# pl2303.net
KiCad netlist of a schematic drawn in EAGLE
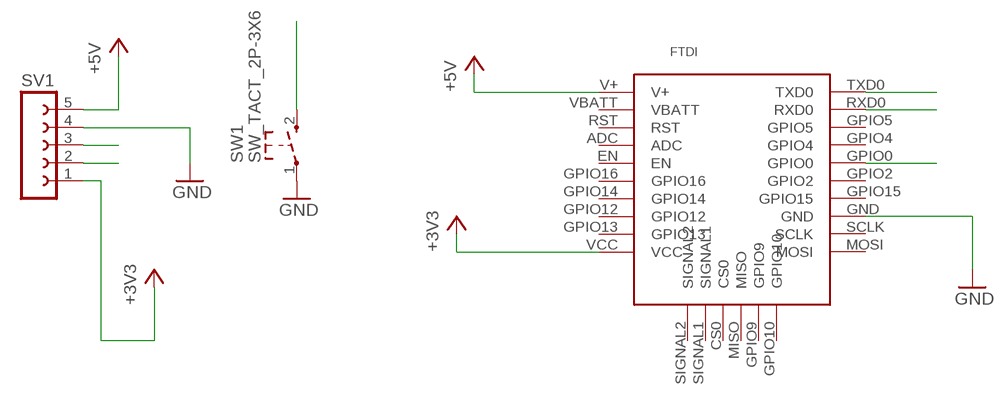
[diagram p0: schematic, sheet 1]

(export (version "E")
  (design (tool "Eeschema 10.0.6"))
  (components
    (comp (ref "FTDI")
      (value "ESP-BOARD")
      (footprint "eagle-import:ESP-BOARD")
      (libsource (lib "eagle-import") (part "ESP-BOARD"))
    )
    (comp (ref "SV1")
      (value "FE05-1")
      (footprint "eagle-import:FE05-1")
      (libsource (lib "eagle-import") (part "FE05-1"))
    )
    (comp (ref "SW1")
      (value "SW_TACT_2P-3X6")
      (footprint "eagle-import:SW_TACT_3X6")
      (libsource (lib "eagle-import") (part "SW_TACT_2P-3X6"))
    )
  )
  (nets
    (net (code "1") (name "+3V3") (class "Default")
      (node (ref "FTDI") (pin "VCC") (pinfunction "VCC_VCC") (pintype "power_in"))
      (node (ref "SV1") (pin "1") (pinfunction "1_1") (pintype "passive"))
    )
    (net (code "2") (name "+5V") (class "Default")
      (node (ref "FTDI") (pin "V+") (pinfunction "V+_V+") (pintype "power_in"))
      (node (ref "SV1") (pin "5") (pinfunction "5_5") (pintype "passive"))
    )
    (net (code "3") (name "/GPIO0") (class "Default")
      (node (ref "FTDI") (pin "GPIO0") (pinfunction "GPIO0_GPIO0") (pintype "bidirectional"))
      (node (ref "SW1") (pin "2") (pinfunction "3_2") (pintype "passive"))
    )
    (net (code "4") (name "/RXD0") (class "Default")
      (node (ref "FTDI") (pin "RXD0") (pinfunction "RXD0_RXD0") (pintype "bidirectional"))
      (node (ref "SV1") (pin "2") (pinfunction "2_2") (pintype "passive"))
    )
    (net (code "5") (name "/TXD0") (class "Default")
      (node (ref "FTDI") (pin "TXD0") (pinfunction "TXD0_TXD0") (pintype "bidirectional"))
      (node (ref "SV1") (pin "3") (pinfunction "3_3") (pintype "passive"))
    )
    (net (code "6") (name "/VBATT") (class "Default")
      (node (ref "FTDI") (pin "VBATT") (pinfunction "VBATT_VBATT") (pintype "power_in"))
    )
    (net (code "7") (name "GND") (class "Default")
      (node (ref "FTDI") (pin "GND") (pinfunction "GND_GND") (pintype "power_in"))
      (node (ref "SV1") (pin "4") (pinfunction "4_4") (pintype "passive"))
      (node (ref "SW1") (pin "1") (pinfunction "1_1") (pintype "passive"))
    )
    (net (code "8") (name "unconnected-(FTDI-PadADC)") (class "Default")
      (node (ref "FTDI") (pin "ADC") (pinfunction "ADC_ADC") (pintype "bidirectional"))
    )
    (net (code "9") (name "unconnected-(FTDI-PadCS0)") (class "Default")
      (node (ref "FTDI") (pin "CS0") (pinfunction "CS0_CS0") (pintype "bidirectional"))
    )
    (net (code "10") (name "unconnected-(FTDI-PadEN)") (class "Default")
      (node (ref "FTDI") (pin "EN") (pinfunction "EN_EN") (pintype "bidirectional"))
    )
    (net (code "11") (name "unconnected-(FTDI-PadGPIO2)") (class "Default")
      (node (ref "FTDI") (pin "GPIO2") (pinfunction "GPIO2_GPIO2") (pintype "bidirectional"))
    )
    (net (code "12") (name "unconnected-(FTDI-PadGPIO4)") (class "Default")
      (node (ref "FTDI") (pin "GPIO4") (pinfunction "GPIO4_GPIO4") (pintype "bidirectional"))
    )
    (net (code "13") (name "unconnected-(FTDI-PadGPIO5)") (class "Default")
      (node (ref "FTDI") (pin "GPIO5") (pinfunction "GPIO5_GPIO5") (pintype "bidirectional"))
    )
    (net (code "14") (name "unconnected-(FTDI-PadGPIO9)") (class "Default")
      (node (ref "FTDI") (pin "GPIO9") (pinfunction "GPIO9_GPIO9") (pintype "bidirectional"))
    )
    (net (code "15") (name "unconnected-(FTDI-PadGPIO10)") (class "Default")
      (node (ref "FTDI") (pin "GPIO10") (pinfunction "GPIO10_GPIO10") (pintype "bidirectional"))
    )
    (net (code "16") (name "unconnected-(FTDI-PadGPIO12)") (class "Default")
      (node (ref "FTDI") (pin "GPIO12") (pinfunction "GPIO12_GPIO12") (pintype "bidirectional"))
    )
    (net (code "17") (name "unconnected-(FTDI-PadGPIO13)") (class "Default")
      (node (ref "FTDI") (pin "GPIO13") (pinfunction "GPIO13_GPIO13") (pintype "bidirectional"))
    )
    (net (code "18") (name "unconnected-(FTDI-PadGPIO14)") (class "Default")
      (node (ref "FTDI") (pin "GPIO14") (pinfunction "GPIO14_GPIO14") (pintype "bidirectional"))
    )
    (net (code "19") (name "unconnected-(FTDI-PadGPIO15)") (class "Default")
      (node (ref "FTDI") (pin "GPIO15") (pinfunction "GPIO15_GPIO15") (pintype "bidirectional"))
    )
    (net (code "20") (name "unconnected-(FTDI-PadGPIO16)") (class "Default")
      (node (ref "FTDI") (pin "GPIO16") (pinfunction "GPIO16_GPIO16") (pintype "bidirectional"))
    )
    (net (code "21") (name "unconnected-(FTDI-PadMISO)") (class "Default")
      (node (ref "FTDI") (pin "MISO") (pinfunction "MISO_MISO") (pintype "bidirectional"))
    )
    (net (code "22") (name "unconnected-(FTDI-PadMOSI)") (class "Default")
      (node (ref "FTDI") (pin "MOSI") (pinfunction "MOSI_MOSI") (pintype "bidirectional"))
    )
    (net (code "23") (name "unconnected-(FTDI-PadRST)") (class "Default")
      (node (ref "FTDI") (pin "RST") (pinfunction "RST_RST") (pintype "bidirectional"))
    )
    (net (code "24") (name "unconnected-(FTDI-PadSCLK)") (class "Default")
      (node (ref "FTDI") (pin "SCLK") (pinfunction "SCLK_SCLK") (pintype "bidirectional"))
    )
    (net (code "25") (name "unconnected-(FTDI-PadSIGNAL1)") (class "Default")
      (node (ref "FTDI") (pin "SIGNAL1") (pinfunction "SIGNAL1_SIGNAL1") (pintype "bidirectional"))
    )
    (net (code "26") (name "unconnected-(FTDI-PadSIGNAL2)") (class "Default")
      (node (ref "FTDI") (pin "SIGNAL2") (pinfunction "SIGNAL2_SIGNAL2") (pintype "bidirectional"))
    )
  )
)
